# ethernet_chip_board.net
KiCad netlist of a schematic drawn in EAGLE
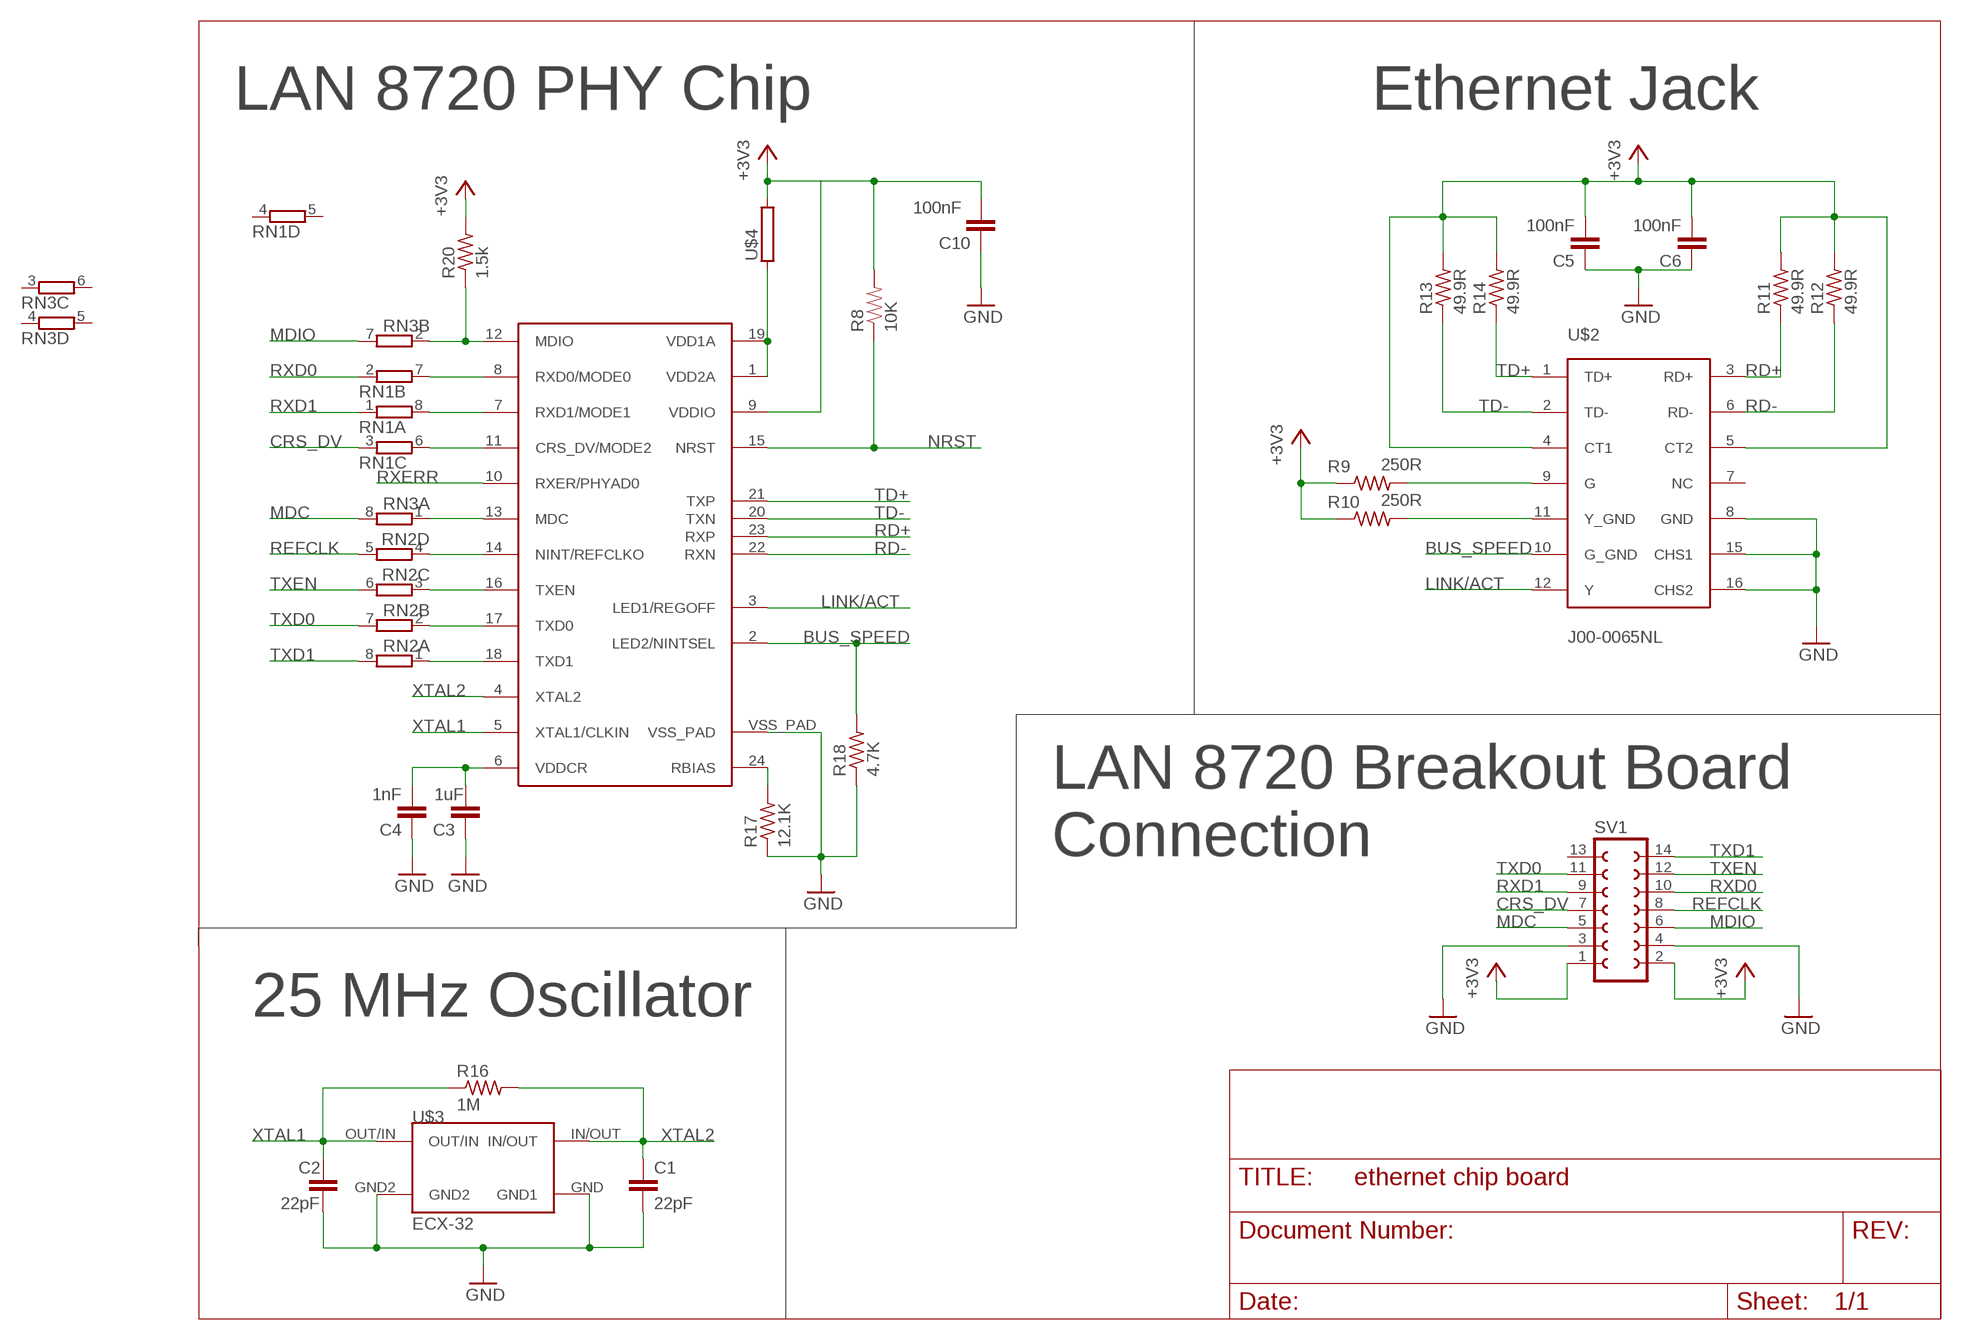
[diagram p0: schematic, sheet 1]

(export (version "E")
  (design (tool "Eeschema 10.0.6"))
  (components
    (comp (ref "C1")
      (value "22pF")
      (footprint "eagle-import:C0603")
      (libsource (lib "eagle-import") (part "CC0603"))
    )
    (comp (ref "C2")
      (value "22pF")
      (footprint "eagle-import:C0603")
      (libsource (lib "eagle-import") (part "CC0603"))
    )
    (comp (ref "C3")
      (value "1uF")
      (footprint "eagle-import:C0603")
      (libsource (lib "eagle-import") (part "CC0603"))
    )
    (comp (ref "C4")
      (value "1nF")
      (footprint "eagle-import:C0603")
      (libsource (lib "eagle-import") (part "CC0603"))
    )
    (comp (ref "C5")
      (value "100nF")
      (footprint "eagle-import:C0603")
      (libsource (lib "eagle-import") (part "CC0603"))
    )
    (comp (ref "C6")
      (value "100nF")
      (footprint "eagle-import:C0603")
      (libsource (lib "eagle-import") (part "CC0603"))
    )
    (comp (ref "C10")
      (value "100nF")
      (footprint "eagle-import:C0603")
      (libsource (lib "eagle-import") (part "CC0603"))
    )
    (comp (ref "R8")
      (value "10K")
      (footprint "eagle-import:0603-RES")
      (libsource (lib "eagle-import") (part "RESISTOR0603-RES"))
    )
    (comp (ref "R9")
      (value "250R")
      (footprint "eagle-import:R0603")
      (libsource (lib "eagle-import") (part "R-US_R0603"))
    )
    (comp (ref "R10")
      (value "250R")
      (footprint "eagle-import:R0603")
      (libsource (lib "eagle-import") (part "R-US_R0603"))
    )
    (comp (ref "R11")
      (value "49.9R")
      (footprint "eagle-import:R0603")
      (libsource (lib "eagle-import") (part "R-US_R0603"))
    )
    (comp (ref "R12")
      (value "49.9R")
      (footprint "eagle-import:R0603")
      (libsource (lib "eagle-import") (part "R-US_R0603"))
    )
    (comp (ref "R13")
      (value "49.9R")
      (footprint "eagle-import:R0603")
      (libsource (lib "eagle-import") (part "R-US_R0603"))
    )
    (comp (ref "R14")
      (value "49.9R")
      (footprint "eagle-import:R0603")
      (libsource (lib "eagle-import") (part "R-US_R0603"))
    )
    (comp (ref "R16")
      (value "1M")
      (footprint "eagle-import:R0603")
      (libsource (lib "eagle-import") (part "R-US_R0603"))
    )
    (comp (ref "R17")
      (value "12.1K")
      (footprint "eagle-import:R0603")
      (libsource (lib "eagle-import") (part "R-US_R0603"))
    )
    (comp (ref "R18")
      (value "4.7K")
      (footprint "eagle-import:R0603")
      (libsource (lib "eagle-import") (part "R-US_R0603"))
    )
    (comp (ref "R20")
      (value "1.5k")
      (footprint "eagle-import:R0603")
      (libsource (lib "eagle-import") (part "R-US_R0603"))
    )
    (comp (ref "RN1")
      (value "4R-NCAY16")
      (footprint "eagle-import:CAY16")
      (libsource (lib "eagle-import") (part "4R-NCAY16"))
    )
    (comp (ref "RN2")
      (value "4R-NCAY16")
      (footprint "eagle-import:CAY16")
      (libsource (lib "eagle-import") (part "4R-NCAY16"))
    )
    (comp (ref "RN3")
      (value "4R-NCAY16")
      (footprint "eagle-import:CAY16")
      (libsource (lib "eagle-import") (part "4R-NCAY16"))
    )
    (comp (ref "SV1")
      (value "FE07-2")
      (footprint "eagle-import:FE07-2")
      (libsource (lib "eagle-import") (part "FE07-2"))
    )
    (comp (ref "U$1")
      (value "LAN8720LAN8720")
      (footprint "eagle-import:24-QFN")
      (libsource (lib "eagle-import") (part "LAN8720LAN8720"))
    )
    (comp (ref "U$2")
      (value "J00-0065NL")
      (footprint "eagle-import:J00-0065NL")
      (libsource (lib "eagle-import") (part "J00-0065NL"))
    )
    (comp (ref "U$3")
      (value "ECX-32")
      (footprint "eagle-import:ECX-32")
      (libsource (lib "eagle-import") (part "ECX-32"))
    )
    (comp (ref "U$4")
      (value "553-2382-1-ND")
      (footprint "eagle-import:0603")
      (libsource (lib "eagle-import") (part "553-2382-1-ND"))
    )
  )
  (nets
    (net (code "1") (name "+3V3") (class "Default")
      (node (ref "C10") (pin "2") (pinfunction "2_2") (pintype "passive"))
      (node (ref "C5") (pin "2") (pinfunction "2_2") (pintype "passive"))
      (node (ref "C6") (pin "2") (pinfunction "2_2") (pintype "passive"))
      (node (ref "R10") (pin "1") (pinfunction "1_1") (pintype "passive"))
      (node (ref "R11") (pin "2") (pinfunction "2_2") (pintype "passive"))
      (node (ref "R12") (pin "2") (pinfunction "2_2") (pintype "passive"))
      (node (ref "R13") (pin "2") (pinfunction "2_2") (pintype "passive"))
      (node (ref "R14") (pin "2") (pinfunction "2_2") (pintype "passive"))
      (node (ref "R20") (pin "2") (pinfunction "2_2") (pintype "passive"))
      (node (ref "R8") (pin "2") (pinfunction "2_2") (pintype "passive"))
      (node (ref "R9") (pin "1") (pinfunction "1_1") (pintype "passive"))
      (node (ref "SV1") (pin "1") (pinfunction "1_1") (pintype "passive"))
      (node (ref "SV1") (pin "2") (pinfunction "2_2") (pintype "passive"))
      (node (ref "U$1") (pin "9") (pinfunction "VDDIO_9") (pintype "bidirectional"))
      (node (ref "U$2") (pin "4") (pinfunction "CT1_4") (pintype "bidirectional"))
      (node (ref "U$2") (pin "5") (pinfunction "CT2_5") (pintype "bidirectional"))
      (node (ref "U$4") (pin "2") (pinfunction "2_2") (pintype "passive"))
    )
    (net (code "2") (name "/BUS_SPEED") (class "Default")
      (node (ref "R18") (pin "2") (pinfunction "2_2") (pintype "passive"))
      (node (ref "U$1") (pin "2") (pinfunction "LED2/NINTSEL_2") (pintype "bidirectional"))
      (node (ref "U$2") (pin "10") (pinfunction "G_GND_10") (pintype "bidirectional"))
    )
    (net (code "3") (name "/CRS_DV") (class "Default")
      (node (ref "RN1") (pin "3") (pinfunction "1_3") (pintype "passive"))
      (node (ref "SV1") (pin "7") (pinfunction "7_7") (pintype "passive"))
    )
    (net (code "4") (name "/LINK{slash}ACT") (class "Default")
      (node (ref "U$1") (pin "3") (pinfunction "LED1/REGOFF_3") (pintype "bidirectional"))
      (node (ref "U$2") (pin "12") (pinfunction "Y_12") (pintype "bidirectional"))
    )
    (net (code "5") (name "/MDC") (class "Default")
      (node (ref "RN3") (pin "8") (pinfunction "2_8") (pintype "passive"))
      (node (ref "SV1") (pin "5") (pinfunction "5_5") (pintype "passive"))
    )
    (net (code "6") (name "/MDIO") (class "Default")
      (node (ref "RN3") (pin "7") (pinfunction "2_7") (pintype "passive"))
      (node (ref "SV1") (pin "6") (pinfunction "6_6") (pintype "passive"))
    )
    (net (code "7") (name "/NRST") (class "Default")
      (node (ref "R8") (pin "1") (pinfunction "1_1") (pintype "passive"))
      (node (ref "U$1") (pin "15") (pinfunction "NRST_15") (pintype "bidirectional"))
    )
    (net (code "8") (name "/RD+") (class "Default")
      (node (ref "R11") (pin "1") (pinfunction "1_1") (pintype "passive"))
      (node (ref "U$1") (pin "23") (pinfunction "RXP_23") (pintype "bidirectional"))
      (node (ref "U$2") (pin "3") (pinfunction "RD+_3") (pintype "bidirectional"))
    )
    (net (code "9") (name "/RD-") (class "Default")
      (node (ref "R12") (pin "1") (pinfunction "1_1") (pintype "passive"))
      (node (ref "U$1") (pin "22") (pinfunction "RXN_22") (pintype "bidirectional"))
      (node (ref "U$2") (pin "6") (pinfunction "RD-_6") (pintype "bidirectional"))
    )
    (net (code "10") (name "/REFCLK") (class "Default")
      (node (ref "RN2") (pin "5") (pinfunction "2_5") (pintype "passive"))
      (node (ref "SV1") (pin "8") (pinfunction "8_8") (pintype "passive"))
    )
    (net (code "11") (name "/RXD0") (class "Default")
      (node (ref "RN1") (pin "2") (pinfunction "1_2") (pintype "passive"))
      (node (ref "SV1") (pin "10") (pinfunction "10_10") (pintype "passive"))
    )
    (net (code "12") (name "/RXD1") (class "Default")
      (node (ref "RN1") (pin "1") (pinfunction "1_1") (pintype "passive"))
      (node (ref "SV1") (pin "9") (pinfunction "9_9") (pintype "passive"))
    )
    (net (code "13") (name "/RXERR") (class "Default")
      (node (ref "U$1") (pin "10") (pinfunction "RXER/PHYAD0_10") (pintype "bidirectional"))
    )
    (net (code "14") (name "/TD+") (class "Default")
      (node (ref "R14") (pin "1") (pinfunction "1_1") (pintype "passive"))
      (node (ref "U$1") (pin "21") (pinfunction "TXP_21") (pintype "bidirectional"))
      (node (ref "U$2") (pin "1") (pinfunction "TD+_1") (pintype "bidirectional"))
    )
    (net (code "15") (name "/TD-") (class "Default")
      (node (ref "R13") (pin "1") (pinfunction "1_1") (pintype "passive"))
      (node (ref "U$1") (pin "20") (pinfunction "TXN_20") (pintype "bidirectional"))
      (node (ref "U$2") (pin "2") (pinfunction "TD-_2") (pintype "bidirectional"))
    )
    (net (code "16") (name "/TXD0") (class "Default")
      (node (ref "RN2") (pin "7") (pinfunction "2_7") (pintype "passive"))
      (node (ref "SV1") (pin "11") (pinfunction "11_11") (pintype "passive"))
    )
    (net (code "17") (name "/TXD1") (class "Default")
      (node (ref "RN2") (pin "8") (pinfunction "2_8") (pintype "passive"))
      (node (ref "SV1") (pin "14") (pinfunction "14_14") (pintype "passive"))
    )
    (net (code "18") (name "/TXEN") (class "Default")
      (node (ref "RN2") (pin "6") (pinfunction "2_6") (pintype "passive"))
      (node (ref "SV1") (pin "12") (pinfunction "12_12") (pintype "passive"))
    )
    (net (code "19") (name "/XTAL1") (class "Default")
      (node (ref "C2") (pin "1") (pinfunction "1_1") (pintype "passive"))
      (node (ref "R16") (pin "1") (pinfunction "1_1") (pintype "passive"))
      (node (ref "U$1") (pin "5") (pinfunction "XTAL1/CLKIN_5") (pintype "bidirectional"))
      (node (ref "U$3") (pin "OUT/IN") (pinfunction "OUT/IN_OUT/IN") (pintype "bidirectional"))
    )
    (net (code "20") (name "/XTAL2") (class "Default")
      (node (ref "C1") (pin "1") (pinfunction "1_1") (pintype "passive"))
      (node (ref "R16") (pin "2") (pinfunction "2_2") (pintype "passive"))
      (node (ref "U$1") (pin "4") (pinfunction "XTAL2_4") (pintype "bidirectional"))
      (node (ref "U$3") (pin "IN/OUT") (pinfunction "IN/OUT_IN/OUT") (pintype "bidirectional"))
    )
    (net (code "21") (name "GND") (class "Default")
      (node (ref "C1") (pin "2") (pinfunction "2_2") (pintype "passive"))
      (node (ref "C10") (pin "1") (pinfunction "1_1") (pintype "passive"))
      (node (ref "C2") (pin "2") (pinfunction "2_2") (pintype "passive"))
      (node (ref "C3") (pin "1") (pinfunction "1_1") (pintype "passive"))
      (node (ref "C4") (pin "1") (pinfunction "1_1") (pintype "passive"))
      (node (ref "C5") (pin "1") (pinfunction "1_1") (pintype "passive"))
      (node (ref "C6") (pin "1") (pinfunction "1_1") (pintype "passive"))
      (node (ref "R17") (pin "1") (pinfunction "1_1") (pintype "passive"))
      (node (ref "R18") (pin "1") (pinfunction "1_1") (pintype "passive"))
      (node (ref "SV1") (pin "3") (pinfunction "3_3") (pintype "passive"))
      (node (ref "SV1") (pin "4") (pinfunction "4_4") (pintype "passive"))
      (node (ref "U$1") (pin "VSS_PAD") (pinfunction "VSS_PAD_VSS_PAD") (pintype "bidirectional"))
      (node (ref "U$2") (pin "15") (pinfunction "CHS1_15") (pintype "bidirectional"))
      (node (ref "U$2") (pin "16") (pinfunction "CHS2_16") (pintype "bidirectional"))
      (node (ref "U$2") (pin "8") (pinfunction "GND_8") (pintype "bidirectional"))
      (node (ref "U$3") (pin "GND") (pinfunction "GND1_GND") (pintype "bidirectional"))
      (node (ref "U$3") (pin "GND2") (pinfunction "GND2_GND2") (pintype "bidirectional"))
    )
    (net (code "22") (name "Net-(RN1A-2)") (class "Default")
      (node (ref "RN1") (pin "8") (pinfunction "2_8") (pintype "passive"))
      (node (ref "U$1") (pin "7") (pinfunction "RXD1/MODE1_7") (pintype "bidirectional"))
    )
    (net (code "23") (name "Net-(RN1B-2)") (class "Default")
      (node (ref "RN1") (pin "7") (pinfunction "2_7") (pintype "passive"))
      (node (ref "U$1") (pin "8") (pinfunction "RXD0/MODE0_8") (pintype "bidirectional"))
    )
    (net (code "24") (name "Net-(RN1C-2)") (class "Default")
      (node (ref "RN1") (pin "6") (pinfunction "2_6") (pintype "passive"))
      (node (ref "U$1") (pin "11") (pinfunction "CRS_DV/MODE2_11") (pintype "bidirectional"))
    )
    (net (code "25") (name "Net-(RN2B-1)") (class "Default")
      (node (ref "RN2") (pin "2") (pinfunction "1_2") (pintype "passive"))
      (node (ref "U$1") (pin "17") (pinfunction "TXD0_17") (pintype "bidirectional"))
    )
    (net (code "26") (name "Net-(RN2C-1)") (class "Default")
      (node (ref "RN2") (pin "3") (pinfunction "1_3") (pintype "passive"))
      (node (ref "U$1") (pin "16") (pinfunction "TXEN_16") (pintype "bidirectional"))
    )
    (net (code "27") (name "Net-(RN2D-1)") (class "Default")
      (node (ref "RN2") (pin "4") (pinfunction "1_4") (pintype "passive"))
      (node (ref "U$1") (pin "14") (pinfunction "NINT/REFCLKO_14") (pintype "bidirectional"))
    )
    (net (code "28") (name "Net-(RN3B-1)") (class "Default")
      (node (ref "R20") (pin "1") (pinfunction "1_1") (pintype "passive"))
      (node (ref "RN3") (pin "2") (pinfunction "1_2") (pintype "passive"))
      (node (ref "U$1") (pin "12") (pinfunction "MDIO_12") (pintype "bidirectional"))
    )
    (net (code "29") (name "Net-(U$1-MDC)") (class "Default")
      (node (ref "RN3") (pin "1") (pinfunction "1_1") (pintype "passive"))
      (node (ref "U$1") (pin "13") (pinfunction "MDC_13") (pintype "bidirectional"))
    )
    (net (code "30") (name "Net-(U$1-RBIAS)") (class "Default")
      (node (ref "R17") (pin "2") (pinfunction "2_2") (pintype "passive"))
      (node (ref "U$1") (pin "24") (pinfunction "RBIAS_24") (pintype "bidirectional"))
    )
    (net (code "31") (name "Net-(U$1-TXD1)") (class "Default")
      (node (ref "RN2") (pin "1") (pinfunction "1_1") (pintype "passive"))
      (node (ref "U$1") (pin "18") (pinfunction "TXD1_18") (pintype "bidirectional"))
    )
    (net (code "32") (name "Net-(U$1-VDD1A)") (class "Default")
      (node (ref "U$1") (pin "1") (pinfunction "VDD2A_1") (pintype "bidirectional"))
      (node (ref "U$1") (pin "19") (pinfunction "VDD1A_19") (pintype "bidirectional"))
      (node (ref "U$4") (pin "1") (pinfunction "1_1") (pintype "passive"))
    )
    (net (code "33") (name "Net-(U$1-VDDCR)") (class "Default")
      (node (ref "C3") (pin "2") (pinfunction "2_2") (pintype "passive"))
      (node (ref "C4") (pin "2") (pinfunction "2_2") (pintype "passive"))
      (node (ref "U$1") (pin "6") (pinfunction "VDDCR_6") (pintype "bidirectional"))
    )
    (net (code "34") (name "Net-(U$2-G)") (class "Default")
      (node (ref "R9") (pin "2") (pinfunction "2_2") (pintype "passive"))
      (node (ref "U$2") (pin "9") (pinfunction "G_9") (pintype "bidirectional"))
    )
    (net (code "35") (name "Net-(U$2-Y_GND)") (class "Default")
      (node (ref "R10") (pin "2") (pinfunction "2_2") (pintype "passive"))
      (node (ref "U$2") (pin "11") (pinfunction "Y_GND_11") (pintype "bidirectional"))
    )
    (net (code "36") (name "unconnected-(RN1D-1-Pad4)") (class "Default")
      (node (ref "RN1") (pin "4") (pinfunction "1_4") (pintype "passive"))
    )
    (net (code "37") (name "unconnected-(RN1D-2-Pad5)") (class "Default")
      (node (ref "RN1") (pin "5") (pinfunction "2_5") (pintype "passive"))
    )
    (net (code "38") (name "unconnected-(RN3C-1-Pad3)") (class "Default")
      (node (ref "RN3") (pin "3") (pinfunction "1_3") (pintype "passive"))
    )
    (net (code "39") (name "unconnected-(RN3C-2-Pad6)") (class "Default")
      (node (ref "RN3") (pin "6") (pinfunction "2_6") (pintype "passive"))
    )
    (net (code "40") (name "unconnected-(RN3D-1-Pad4)") (class "Default")
      (node (ref "RN3") (pin "4") (pinfunction "1_4") (pintype "passive"))
    )
    (net (code "41") (name "unconnected-(RN3D-2-Pad5)") (class "Default")
      (node (ref "RN3") (pin "5") (pinfunction "2_5") (pintype "passive"))
    )
    (net (code "42") (name "unconnected-(SV1-Pad13)") (class "Default")
      (node (ref "SV1") (pin "13") (pinfunction "13_13") (pintype "passive"))
    )
    (net (code "43") (name "unconnected-(U$2-NC-Pad7)") (class "Default")
      (node (ref "U$2") (pin "7") (pinfunction "NC_7") (pintype "bidirectional"))
    )
  )
)
